# Thermistor_Hysteresis_Example.net
KiCad netlist of a schematic drawn in EAGLE
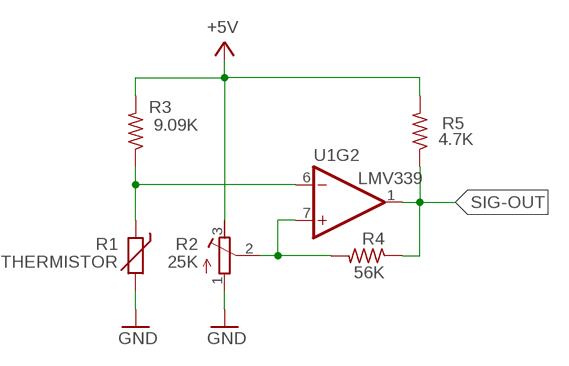
[diagram p0: schematic, sheet 1]

(export (version "E")
  (design (tool "Eeschema 10.0.6"))
  (components
    (comp (ref "R1")
      (value "THERMISTOR")
      (footprint "eagle-import:R-7,5")
      (libsource (lib "eagle-import") (part "THERMISTOR-7,5"))
    )
    (comp (ref "R2")
      (value "25K")
      (footprint "eagle-import:RTRIM3296Y")
      (libsource (lib "eagle-import") (part "R-TRIMM3296Y"))
    )
    (comp (ref "R3")
      (value "9.09K")
      (footprint "eagle-import:R0805")
      (libsource (lib "eagle-import") (part "R-US_R0805"))
    )
    (comp (ref "R4")
      (value "56K")
      (footprint "eagle-import:R0805")
      (libsource (lib "eagle-import") (part "R-US_R0805"))
    )
    (comp (ref "R5")
      (value "4.7K")
      (footprint "eagle-import:R0805")
      (libsource (lib "eagle-import") (part "R-US_R0805"))
    )
    (comp (ref "U1")
      (value "LMV339")
      (footprint "eagle-import:SOIC127P599X175-14")
      (libsource (lib "eagle-import") (part "LM339SOIC-14"))
    )
  )
  (nets
    (net (code "1") (name "+5V") (class "Default")
      (node (ref "R2") (pin "3") (pinfunction "E_3") (pintype "passive"))
      (node (ref "R3") (pin "2") (pinfunction "2_2") (pintype "passive"))
      (node (ref "R5") (pin "2") (pinfunction "2_2") (pintype "passive"))
    )
    (net (code "2") (name "GND") (class "Default")
      (node (ref "R1") (pin "2") (pinfunction "2_2") (pintype "passive"))
      (node (ref "R2") (pin "1") (pinfunction "A_1") (pintype "passive"))
    )
    (net (code "3") (name "Net-(R2-S)") (class "Default")
      (node (ref "R2") (pin "2") (pinfunction "S_2") (pintype "passive"))
      (node (ref "R4") (pin "2") (pinfunction "2_2") (pintype "passive"))
      (node (ref "U1") (pin "7") (pinfunction "+IN_7") (pintype "input"))
    )
    (net (code "4") (name "Net-(U1B--IN)") (class "Default")
      (node (ref "R1") (pin "1") (pinfunction "1_1") (pintype "passive"))
      (node (ref "R3") (pin "1") (pinfunction "1_1") (pintype "passive"))
      (node (ref "U1") (pin "6") (pinfunction "-IN_6") (pintype "input"))
    )
    (net (code "5") (name "SIG-OUT") (class "Default")
      (node (ref "R4") (pin "1") (pinfunction "1_1") (pintype "passive"))
      (node (ref "R5") (pin "1") (pinfunction "1_1") (pintype "passive"))
      (node (ref "U1") (pin "1") (pinfunction "OUT_1") (pintype "output"))
    )
  )
)
